# my_dac_amp_pwr_v0002.net
KiCad netlist of a schematic drawn in EAGLE
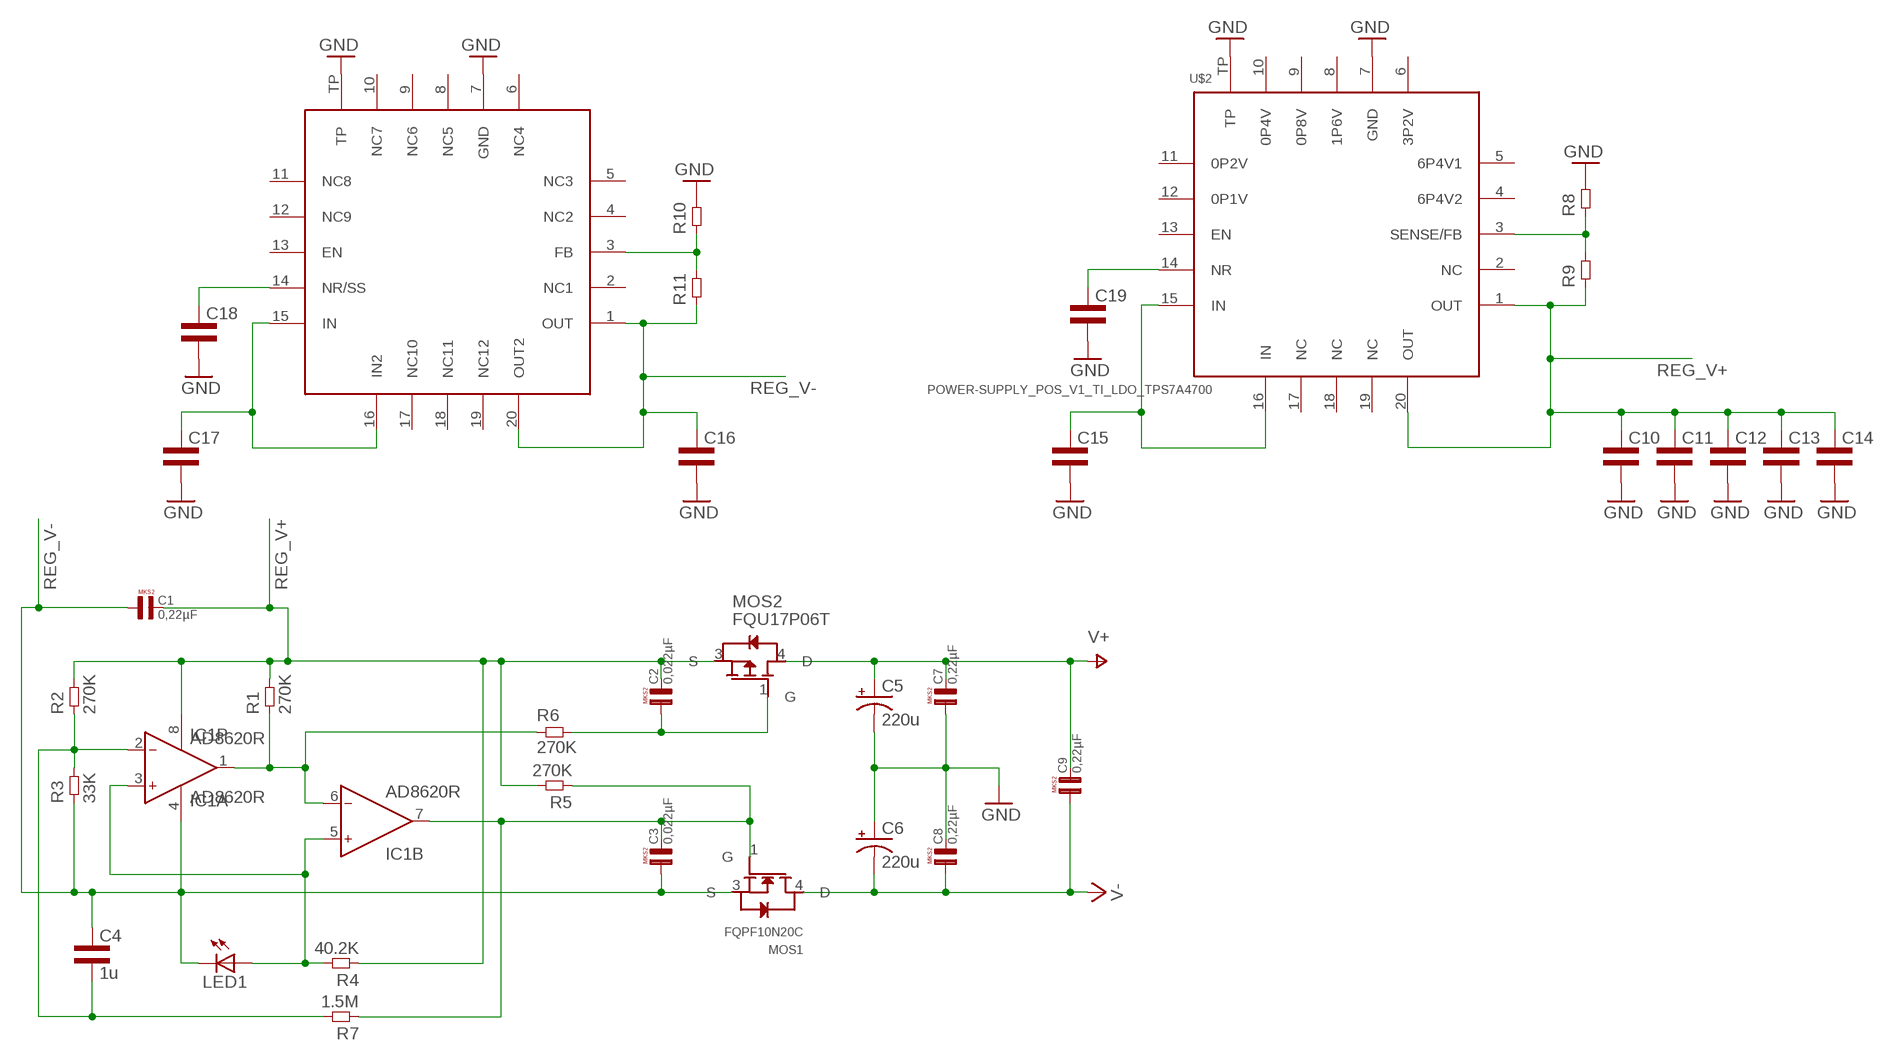
[diagram p0: schematic, sheet 1]

(export (version "E")
  (design (tool "Eeschema 10.0.6"))
  (components
    (comp (ref "C1")
      (value "0,22µF")
      (footprint "eagle-import:R5B3")
      (libsource (lib "eagle-import") (part "0,22µF"))
    )
    (comp (ref "C2")
      (value "0,022µF")
      (footprint "eagle-import:R5B2K5")
      (libsource (lib "eagle-import") (part "0,022µF"))
    )
    (comp (ref "C3")
      (value "0,022µF")
      (footprint "eagle-import:R5B2K5")
      (libsource (lib "eagle-import") (part "0,022µF"))
    )
    (comp (ref "C4")
      (value "1u")
      (footprint "eagle-import:0805L3")
      (libsource (lib "eagle-import") (part "CAP0805L3"))
    )
    (comp (ref "C5")
      (value "220u")
      (footprint "eagle-import:E5-10,5")
      (libsource (lib "eagle-import") (part "CPOL-USE5-10.5"))
    )
    (comp (ref "C6")
      (value "220u")
      (footprint "eagle-import:E5-10,5")
      (libsource (lib "eagle-import") (part "CPOL-USE5-10.5"))
    )
    (comp (ref "C7")
      (value "0,22µF")
      (footprint "eagle-import:R5B3")
      (libsource (lib "eagle-import") (part "0,22µF"))
    )
    (comp (ref "C8")
      (value "0,22µF")
      (footprint "eagle-import:R5B3")
      (libsource (lib "eagle-import") (part "0,22µF"))
    )
    (comp (ref "C9")
      (value "0,22µF")
      (footprint "eagle-import:R5B3")
      (libsource (lib "eagle-import") (part "0,22µF"))
    )
    (comp (ref "C10")
      (value "CAP0805L3")
      (footprint "eagle-import:0805L3")
      (libsource (lib "eagle-import") (part "CAP0805L3"))
    )
    (comp (ref "C11")
      (value "CAP0805L3")
      (footprint "eagle-import:0805L3")
      (libsource (lib "eagle-import") (part "CAP0805L3"))
    )
    (comp (ref "C12")
      (value "CAP0805L3")
      (footprint "eagle-import:0805L3")
      (libsource (lib "eagle-import") (part "CAP0805L3"))
    )
    (comp (ref "C13")
      (value "CAP0805L3")
      (footprint "eagle-import:0805L3")
      (libsource (lib "eagle-import") (part "CAP0805L3"))
    )
    (comp (ref "C14")
      (value "CAP0805L3")
      (footprint "eagle-import:0805L3")
      (libsource (lib "eagle-import") (part "CAP0805L3"))
    )
    (comp (ref "C15")
      (value "CAP0805L3")
      (footprint "eagle-import:0805L3")
      (libsource (lib "eagle-import") (part "CAP0805L3"))
    )
    (comp (ref "C16")
      (value "CAP0805L3")
      (footprint "eagle-import:0805L3")
      (libsource (lib "eagle-import") (part "CAP0805L3"))
    )
    (comp (ref "C17")
      (value "CAP0805L3")
      (footprint "eagle-import:0805L3")
      (libsource (lib "eagle-import") (part "CAP0805L3"))
    )
    (comp (ref "C18")
      (value "CAP0603L3")
      (footprint "eagle-import:0603L3")
      (libsource (lib "eagle-import") (part "CAP0603L3"))
    )
    (comp (ref "C19")
      (value "CAP0603L3")
      (footprint "eagle-import:0603L3")
      (libsource (lib "eagle-import") (part "CAP0603L3"))
    )
    (comp (ref "IC1")
      (value "AD8620R")
      (footprint "eagle-import:SO8")
      (fields (field (name "MF") "ALTERA CORPORATION") (field (name "MPN") "AD8620ARZ"))
      (libsource (lib "eagle-import") (part "AD8620R"))
    )
    (comp (ref "LED1")
      (value "LED3MM")
      (footprint "eagle-import:LED3MM")
      (libsource (lib "eagle-import") (part "LED3MM"))
    )
    (comp (ref "MOS1")
      (value "FQPF10N20C")
      (footprint "eagle-import:DPAK-3")
      (libsource (lib "eagle-import") (part "MOSFET-N"))
    )
    (comp (ref "MOS2")
      (value "FQU17P06T")
      (footprint "eagle-import:DPAK-3")
      (libsource (lib "eagle-import") (part "MOSFET-P"))
    )
    (comp (ref "R1")
      (value "270K")
      (footprint "eagle-import:0805L3")
      (libsource (lib "eagle-import") (part "RES0805L3"))
    )
    (comp (ref "R2")
      (value "270K")
      (footprint "eagle-import:0805L3")
      (libsource (lib "eagle-import") (part "RES0805L3"))
    )
    (comp (ref "R3")
      (value "33K")
      (footprint "eagle-import:0805L3")
      (libsource (lib "eagle-import") (part "RES0805L3"))
    )
    (comp (ref "R4")
      (value "40.2K")
      (footprint "eagle-import:0805L3")
      (libsource (lib "eagle-import") (part "RES0805L3"))
    )
    (comp (ref "R5")
      (value "270K")
      (footprint "eagle-import:0805L3")
      (libsource (lib "eagle-import") (part "RES0805L3"))
    )
    (comp (ref "R6")
      (value "270K")
      (footprint "eagle-import:0805L3")
      (libsource (lib "eagle-import") (part "RES0805L3"))
    )
    (comp (ref "R7")
      (value "1.5M")
      (footprint "eagle-import:0805L3")
      (libsource (lib "eagle-import") (part "RES0805L3"))
    )
    (comp (ref "R8")
      (value "RES0603L3")
      (footprint "eagle-import:0603L3")
      (libsource (lib "eagle-import") (part "RES0603L3"))
    )
    (comp (ref "R9")
      (value "RES0603L3")
      (footprint "eagle-import:0603L3")
      (libsource (lib "eagle-import") (part "RES0603L3"))
    )
    (comp (ref "R10")
      (value "RES0603L3")
      (footprint "eagle-import:0603L3")
      (libsource (lib "eagle-import") (part "RES0603L3"))
    )
    (comp (ref "R11")
      (value "RES0603L3")
      (footprint "eagle-import:0603L3")
      (libsource (lib "eagle-import") (part "RES0603L3"))
    )
    (comp (ref "U$1")
      (value "POWER-SUPPLY_POS_V1_TI_LDO_TPS7A3301RGWT")
      (footprint "eagle-import:POWER-SUPPLY_POS_V1_TI_LDO_VQFN-20")
      (libsource (lib "eagle-import") (part "POWER-SUPPLY_POS_V1_TI_LDO_TPS7A3301RGWT"))
    )
    (comp (ref "U$2")
      (value "POWER-SUPPLY_POS_V1_TI_LDO_TPS7A4700")
      (footprint "eagle-import:POWER-SUPPLY_POS_V1_TI_LDO_VQFN-20")
      (libsource (lib "eagle-import") (part "POWER-SUPPLY_POS_V1_TI_LDO_TPS7A4700"))
    )
  )
  (nets
    (net (code "1") (name "/REG_V+") (class "Default")
      (node (ref "C1") (pin "2") (pinfunction "2_2") (pintype "passive"))
      (node (ref "C10") (pin "1") (pinfunction "1_1") (pintype "bidirectional"))
      (node (ref "C11") (pin "1") (pinfunction "1_1") (pintype "bidirectional"))
      (node (ref "C12") (pin "1") (pinfunction "1_1") (pintype "bidirectional"))
      (node (ref "C13") (pin "1") (pinfunction "1_1") (pintype "bidirectional"))
      (node (ref "C14") (pin "1") (pinfunction "1_1") (pintype "bidirectional"))
      (node (ref "C2") (pin "2") (pinfunction "2_2") (pintype "passive"))
      (node (ref "IC1") (pin "8") (pinfunction "V+_8") (pintype "power_in"))
      (node (ref "MOS2") (pin "3") (pinfunction "S_3") (pintype "bidirectional"))
      (node (ref "R1") (pin "2") (pinfunction "2_2") (pintype "bidirectional"))
      (node (ref "R2") (pin "2") (pinfunction "2_2") (pintype "bidirectional"))
      (node (ref "R4") (pin "1") (pinfunction "1_1") (pintype "bidirectional"))
      (node (ref "R5") (pin "2") (pinfunction "2_2") (pintype "bidirectional"))
      (node (ref "R9") (pin "P$1") (pinfunction "1_P$1") (pintype "bidirectional"))
      (node (ref "U$2") (pin "1") (pinfunction "OUT_1") (pintype "bidirectional"))
      (node (ref "U$2") (pin "20") (pinfunction "OUT_20") (pintype "bidirectional"))
    )
    (net (code "2") (name "/REG_V-") (class "Default")
      (node (ref "C1") (pin "1") (pinfunction "1_1") (pintype "passive"))
      (node (ref "C16") (pin "1") (pinfunction "1_1") (pintype "bidirectional"))
      (node (ref "C3") (pin "1") (pinfunction "1_1") (pintype "passive"))
      (node (ref "C4") (pin "1") (pinfunction "1_1") (pintype "bidirectional"))
      (node (ref "IC1") (pin "4") (pinfunction "V-_4") (pintype "power_in"))
      (node (ref "LED1") (pin "K") (pinfunction "C_K") (pintype "passive"))
      (node (ref "MOS1") (pin "3") (pinfunction "S_3") (pintype "bidirectional"))
      (node (ref "R11") (pin "P$1") (pinfunction "1_P$1") (pintype "bidirectional"))
      (node (ref "R3") (pin "1") (pinfunction "1_1") (pintype "bidirectional"))
      (node (ref "U$1") (pin "1") (pinfunction "OUT_1") (pintype "bidirectional"))
      (node (ref "U$1") (pin "20") (pinfunction "OUT2_20") (pintype "bidirectional"))
    )
    (net (code "3") (name "GND") (class "Default")
      (node (ref "C10") (pin "2") (pinfunction "2_2") (pintype "bidirectional"))
      (node (ref "C11") (pin "2") (pinfunction "2_2") (pintype "bidirectional"))
      (node (ref "C12") (pin "2") (pinfunction "2_2") (pintype "bidirectional"))
      (node (ref "C13") (pin "2") (pinfunction "2_2") (pintype "bidirectional"))
      (node (ref "C14") (pin "2") (pinfunction "2_2") (pintype "bidirectional"))
      (node (ref "C15") (pin "2") (pinfunction "2_2") (pintype "bidirectional"))
      (node (ref "C16") (pin "2") (pinfunction "2_2") (pintype "bidirectional"))
      (node (ref "C17") (pin "2") (pinfunction "2_2") (pintype "bidirectional"))
      (node (ref "C18") (pin "P$2") (pinfunction "2_P$2") (pintype "bidirectional"))
      (node (ref "C19") (pin "P$2") (pinfunction "2_P$2") (pintype "bidirectional"))
      (node (ref "C5") (pin "-") (pinfunction "-_-") (pintype "passive"))
      (node (ref "C6") (pin "+") (pinfunction "+_+") (pintype "passive"))
      (node (ref "C7") (pin "1") (pinfunction "1_1") (pintype "passive"))
      (node (ref "C8") (pin "2") (pinfunction "2_2") (pintype "passive"))
      (node (ref "R10") (pin "P$2") (pinfunction "2_P$2") (pintype "bidirectional"))
      (node (ref "R8") (pin "P$2") (pinfunction "2_P$2") (pintype "bidirectional"))
      (node (ref "U$1") (pin "7") (pinfunction "GND_7") (pintype "bidirectional"))
      (node (ref "U$1") (pin "TP") (pinfunction "TP_TP") (pintype "bidirectional"))
      (node (ref "U$2") (pin "7") (pinfunction "GND_7") (pintype "bidirectional"))
      (node (ref "U$2") (pin "TP") (pinfunction "TP_TP") (pintype "bidirectional"))
    )
    (net (code "4") (name "Net-(C15-Pad1)") (class "Default")
      (node (ref "C15") (pin "1") (pinfunction "1_1") (pintype "bidirectional"))
      (node (ref "U$2") (pin "15") (pinfunction "IN_15") (pintype "bidirectional"))
      (node (ref "U$2") (pin "16") (pinfunction "IN_16") (pintype "bidirectional"))
    )
    (net (code "5") (name "Net-(C18-1)") (class "Default")
      (node (ref "C18") (pin "P$1") (pinfunction "1_P$1") (pintype "bidirectional"))
      (node (ref "U$1") (pin "14") (pinfunction "NR/SS_14") (pintype "bidirectional"))
    )
    (net (code "6") (name "Net-(C19-1)") (class "Default")
      (node (ref "C19") (pin "P$1") (pinfunction "1_P$1") (pintype "bidirectional"))
      (node (ref "U$2") (pin "14") (pinfunction "NR_14") (pintype "bidirectional"))
    )
    (net (code "7") (name "Net-(IC1A-IN+)") (class "Default")
      (node (ref "IC1") (pin "3") (pinfunction "IN+_3") (pintype "input"))
      (node (ref "IC1") (pin "5") (pinfunction "IN+_5") (pintype "input"))
      (node (ref "LED1") (pin "A") (pinfunction "A_A") (pintype "passive"))
      (node (ref "R4") (pin "2") (pinfunction "2_2") (pintype "bidirectional"))
    )
    (net (code "8") (name "Net-(IC1A-IN-)") (class "Default")
      (node (ref "C4") (pin "2") (pinfunction "2_2") (pintype "bidirectional"))
      (node (ref "IC1") (pin "2") (pinfunction "IN-_2") (pintype "input"))
      (node (ref "R2") (pin "1") (pinfunction "1_1") (pintype "bidirectional"))
      (node (ref "R3") (pin "2") (pinfunction "2_2") (pintype "bidirectional"))
      (node (ref "R7") (pin "2") (pinfunction "2_2") (pintype "bidirectional"))
    )
    (net (code "9") (name "Net-(IC1A-OUT)") (class "Default")
      (node (ref "IC1") (pin "1") (pinfunction "OUT_1") (pintype "output"))
      (node (ref "IC1") (pin "6") (pinfunction "IN-_6") (pintype "input"))
      (node (ref "R1") (pin "1") (pinfunction "1_1") (pintype "bidirectional"))
      (node (ref "R6") (pin "1") (pinfunction "1_1") (pintype "bidirectional"))
    )
    (net (code "10") (name "Net-(IC1B-OUT)") (class "Default")
      (node (ref "C3") (pin "2") (pinfunction "2_2") (pintype "passive"))
      (node (ref "IC1") (pin "7") (pinfunction "OUT_7") (pintype "output"))
      (node (ref "MOS1") (pin "1") (pinfunction "G_1") (pintype "bidirectional"))
      (node (ref "R5") (pin "1") (pinfunction "1_1") (pintype "bidirectional"))
      (node (ref "R7") (pin "1") (pinfunction "1_1") (pintype "bidirectional"))
    )
    (net (code "11") (name "Net-(MOS2-G)") (class "Default")
      (node (ref "C2") (pin "1") (pinfunction "1_1") (pintype "passive"))
      (node (ref "MOS2") (pin "1") (pinfunction "G_1") (pintype "bidirectional"))
      (node (ref "R6") (pin "2") (pinfunction "2_2") (pintype "bidirectional"))
    )
    (net (code "12") (name "Net-(R8-1)") (class "Default")
      (node (ref "R8") (pin "P$1") (pinfunction "1_P$1") (pintype "bidirectional"))
      (node (ref "R9") (pin "P$2") (pinfunction "2_P$2") (pintype "bidirectional"))
      (node (ref "U$2") (pin "3") (pinfunction "SENSE/FB_3") (pintype "bidirectional"))
    )
    (net (code "13") (name "Net-(R10-1)") (class "Default")
      (node (ref "R10") (pin "P$1") (pinfunction "1_P$1") (pintype "bidirectional"))
      (node (ref "R11") (pin "P$2") (pinfunction "2_P$2") (pintype "bidirectional"))
      (node (ref "U$1") (pin "3") (pinfunction "FB_3") (pintype "bidirectional"))
    )
    (net (code "14") (name "Net-(U$1-IN)") (class "Default")
      (node (ref "C17") (pin "1") (pinfunction "1_1") (pintype "bidirectional"))
      (node (ref "U$1") (pin "15") (pinfunction "IN_15") (pintype "bidirectional"))
      (node (ref "U$1") (pin "16") (pinfunction "IN2_16") (pintype "bidirectional"))
    )
    (net (code "15") (name "V+") (class "Default")
      (node (ref "C5") (pin "+") (pinfunction "+_+") (pintype "passive"))
      (node (ref "C7") (pin "2") (pinfunction "2_2") (pintype "passive"))
      (node (ref "C9") (pin "2") (pinfunction "2_2") (pintype "passive"))
      (node (ref "MOS2") (pin "4") (pinfunction "D_4") (pintype "bidirectional"))
    )
    (net (code "16") (name "V-") (class "Default")
      (node (ref "C6") (pin "-") (pinfunction "-_-") (pintype "passive"))
      (node (ref "C8") (pin "1") (pinfunction "1_1") (pintype "passive"))
      (node (ref "C9") (pin "1") (pinfunction "1_1") (pintype "passive"))
      (node (ref "MOS1") (pin "4") (pinfunction "D_4") (pintype "bidirectional"))
    )
    (net (code "17") (name "unconnected-(U$1-EN-Pad13)") (class "Default")
      (node (ref "U$1") (pin "13") (pinfunction "EN_13") (pintype "bidirectional"))
    )
    (net (code "18") (name "unconnected-(U$1-NC1-Pad2)") (class "Default")
      (node (ref "U$1") (pin "2") (pinfunction "NC1_2") (pintype "bidirectional"))
    )
    (net (code "19") (name "unconnected-(U$1-NC2-Pad4)") (class "Default")
      (node (ref "U$1") (pin "4") (pinfunction "NC2_4") (pintype "bidirectional"))
    )
    (net (code "20") (name "unconnected-(U$1-NC3-Pad5)") (class "Default")
      (node (ref "U$1") (pin "5") (pinfunction "NC3_5") (pintype "bidirectional"))
    )
    (net (code "21") (name "unconnected-(U$1-NC4-Pad6)") (class "Default")
      (node (ref "U$1") (pin "6") (pinfunction "NC4_6") (pintype "bidirectional"))
    )
    (net (code "22") (name "unconnected-(U$1-NC5-Pad8)") (class "Default")
      (node (ref "U$1") (pin "8") (pinfunction "NC5_8") (pintype "bidirectional"))
    )
    (net (code "23") (name "unconnected-(U$1-NC6-Pad9)") (class "Default")
      (node (ref "U$1") (pin "9") (pinfunction "NC6_9") (pintype "bidirectional"))
    )
    (net (code "24") (name "unconnected-(U$1-NC7-Pad10)") (class "Default")
      (node (ref "U$1") (pin "10") (pinfunction "NC7_10") (pintype "bidirectional"))
    )
    (net (code "25") (name "unconnected-(U$1-NC8-Pad11)") (class "Default")
      (node (ref "U$1") (pin "11") (pinfunction "NC8_11") (pintype "bidirectional"))
    )
    (net (code "26") (name "unconnected-(U$1-NC9-Pad12)") (class "Default")
      (node (ref "U$1") (pin "12") (pinfunction "NC9_12") (pintype "bidirectional"))
    )
    (net (code "27") (name "unconnected-(U$1-NC10-Pad17)") (class "Default")
      (node (ref "U$1") (pin "17") (pinfunction "NC10_17") (pintype "bidirectional"))
    )
    (net (code "28") (name "unconnected-(U$1-NC11-Pad18)") (class "Default")
      (node (ref "U$1") (pin "18") (pinfunction "NC11_18") (pintype "bidirectional"))
    )
    (net (code "29") (name "unconnected-(U$1-NC12-Pad19)") (class "Default")
      (node (ref "U$1") (pin "19") (pinfunction "NC12_19") (pintype "bidirectional"))
    )
    (net (code "30") (name "unconnected-(U$2-0P1V-Pad12)") (class "Default")
      (node (ref "U$2") (pin "12") (pinfunction "0P1V_12") (pintype "bidirectional"))
    )
    (net (code "31") (name "unconnected-(U$2-0P2V-Pad11)") (class "Default")
      (node (ref "U$2") (pin "11") (pinfunction "0P2V_11") (pintype "bidirectional"))
    )
    (net (code "32") (name "unconnected-(U$2-0P4V-Pad10)") (class "Default")
      (node (ref "U$2") (pin "10") (pinfunction "0P4V_10") (pintype "bidirectional"))
    )
    (net (code "33") (name "unconnected-(U$2-0P8V-Pad9)") (class "Default")
      (node (ref "U$2") (pin "9") (pinfunction "0P8V_9") (pintype "bidirectional"))
    )
    (net (code "34") (name "unconnected-(U$2-1P6V-Pad8)") (class "Default")
      (node (ref "U$2") (pin "8") (pinfunction "1P6V_8") (pintype "bidirectional"))
    )
    (net (code "35") (name "unconnected-(U$2-3P2V-Pad6)") (class "Default")
      (node (ref "U$2") (pin "6") (pinfunction "3P2V_6") (pintype "bidirectional"))
    )
    (net (code "36") (name "unconnected-(U$2-6P4V1-Pad5)") (class "Default")
      (node (ref "U$2") (pin "5") (pinfunction "6P4V1_5") (pintype "bidirectional"))
    )
    (net (code "37") (name "unconnected-(U$2-6P4V2-Pad4)") (class "Default")
      (node (ref "U$2") (pin "4") (pinfunction "6P4V2_4") (pintype "bidirectional"))
    )
    (net (code "38") (name "unconnected-(U$2-EN-Pad13)") (class "Default")
      (node (ref "U$2") (pin "13") (pinfunction "EN_13") (pintype "bidirectional"))
    )
    (net (code "39") (name "unconnected-(U$2-NC-Pad2)") (class "Default")
      (node (ref "U$2") (pin "2") (pinfunction "NC_2") (pintype "bidirectional"))
    )
    (net (code "40") (name "unconnected-(U$2-NC-Pad17)") (class "Default")
      (node (ref "U$2") (pin "17") (pinfunction "NC_17") (pintype "bidirectional"))
    )
    (net (code "41") (name "unconnected-(U$2-NC-Pad18)") (class "Default")
      (node (ref "U$2") (pin "18") (pinfunction "NC_18") (pintype "bidirectional"))
    )
    (net (code "42") (name "unconnected-(U$2-NC-Pad19)") (class "Default")
      (node (ref "U$2") (pin "19") (pinfunction "NC_19") (pintype "bidirectional"))
    )
  )
)
